# stm32.net
KiCad netlist of a schematic drawn in EasyEDA Pro
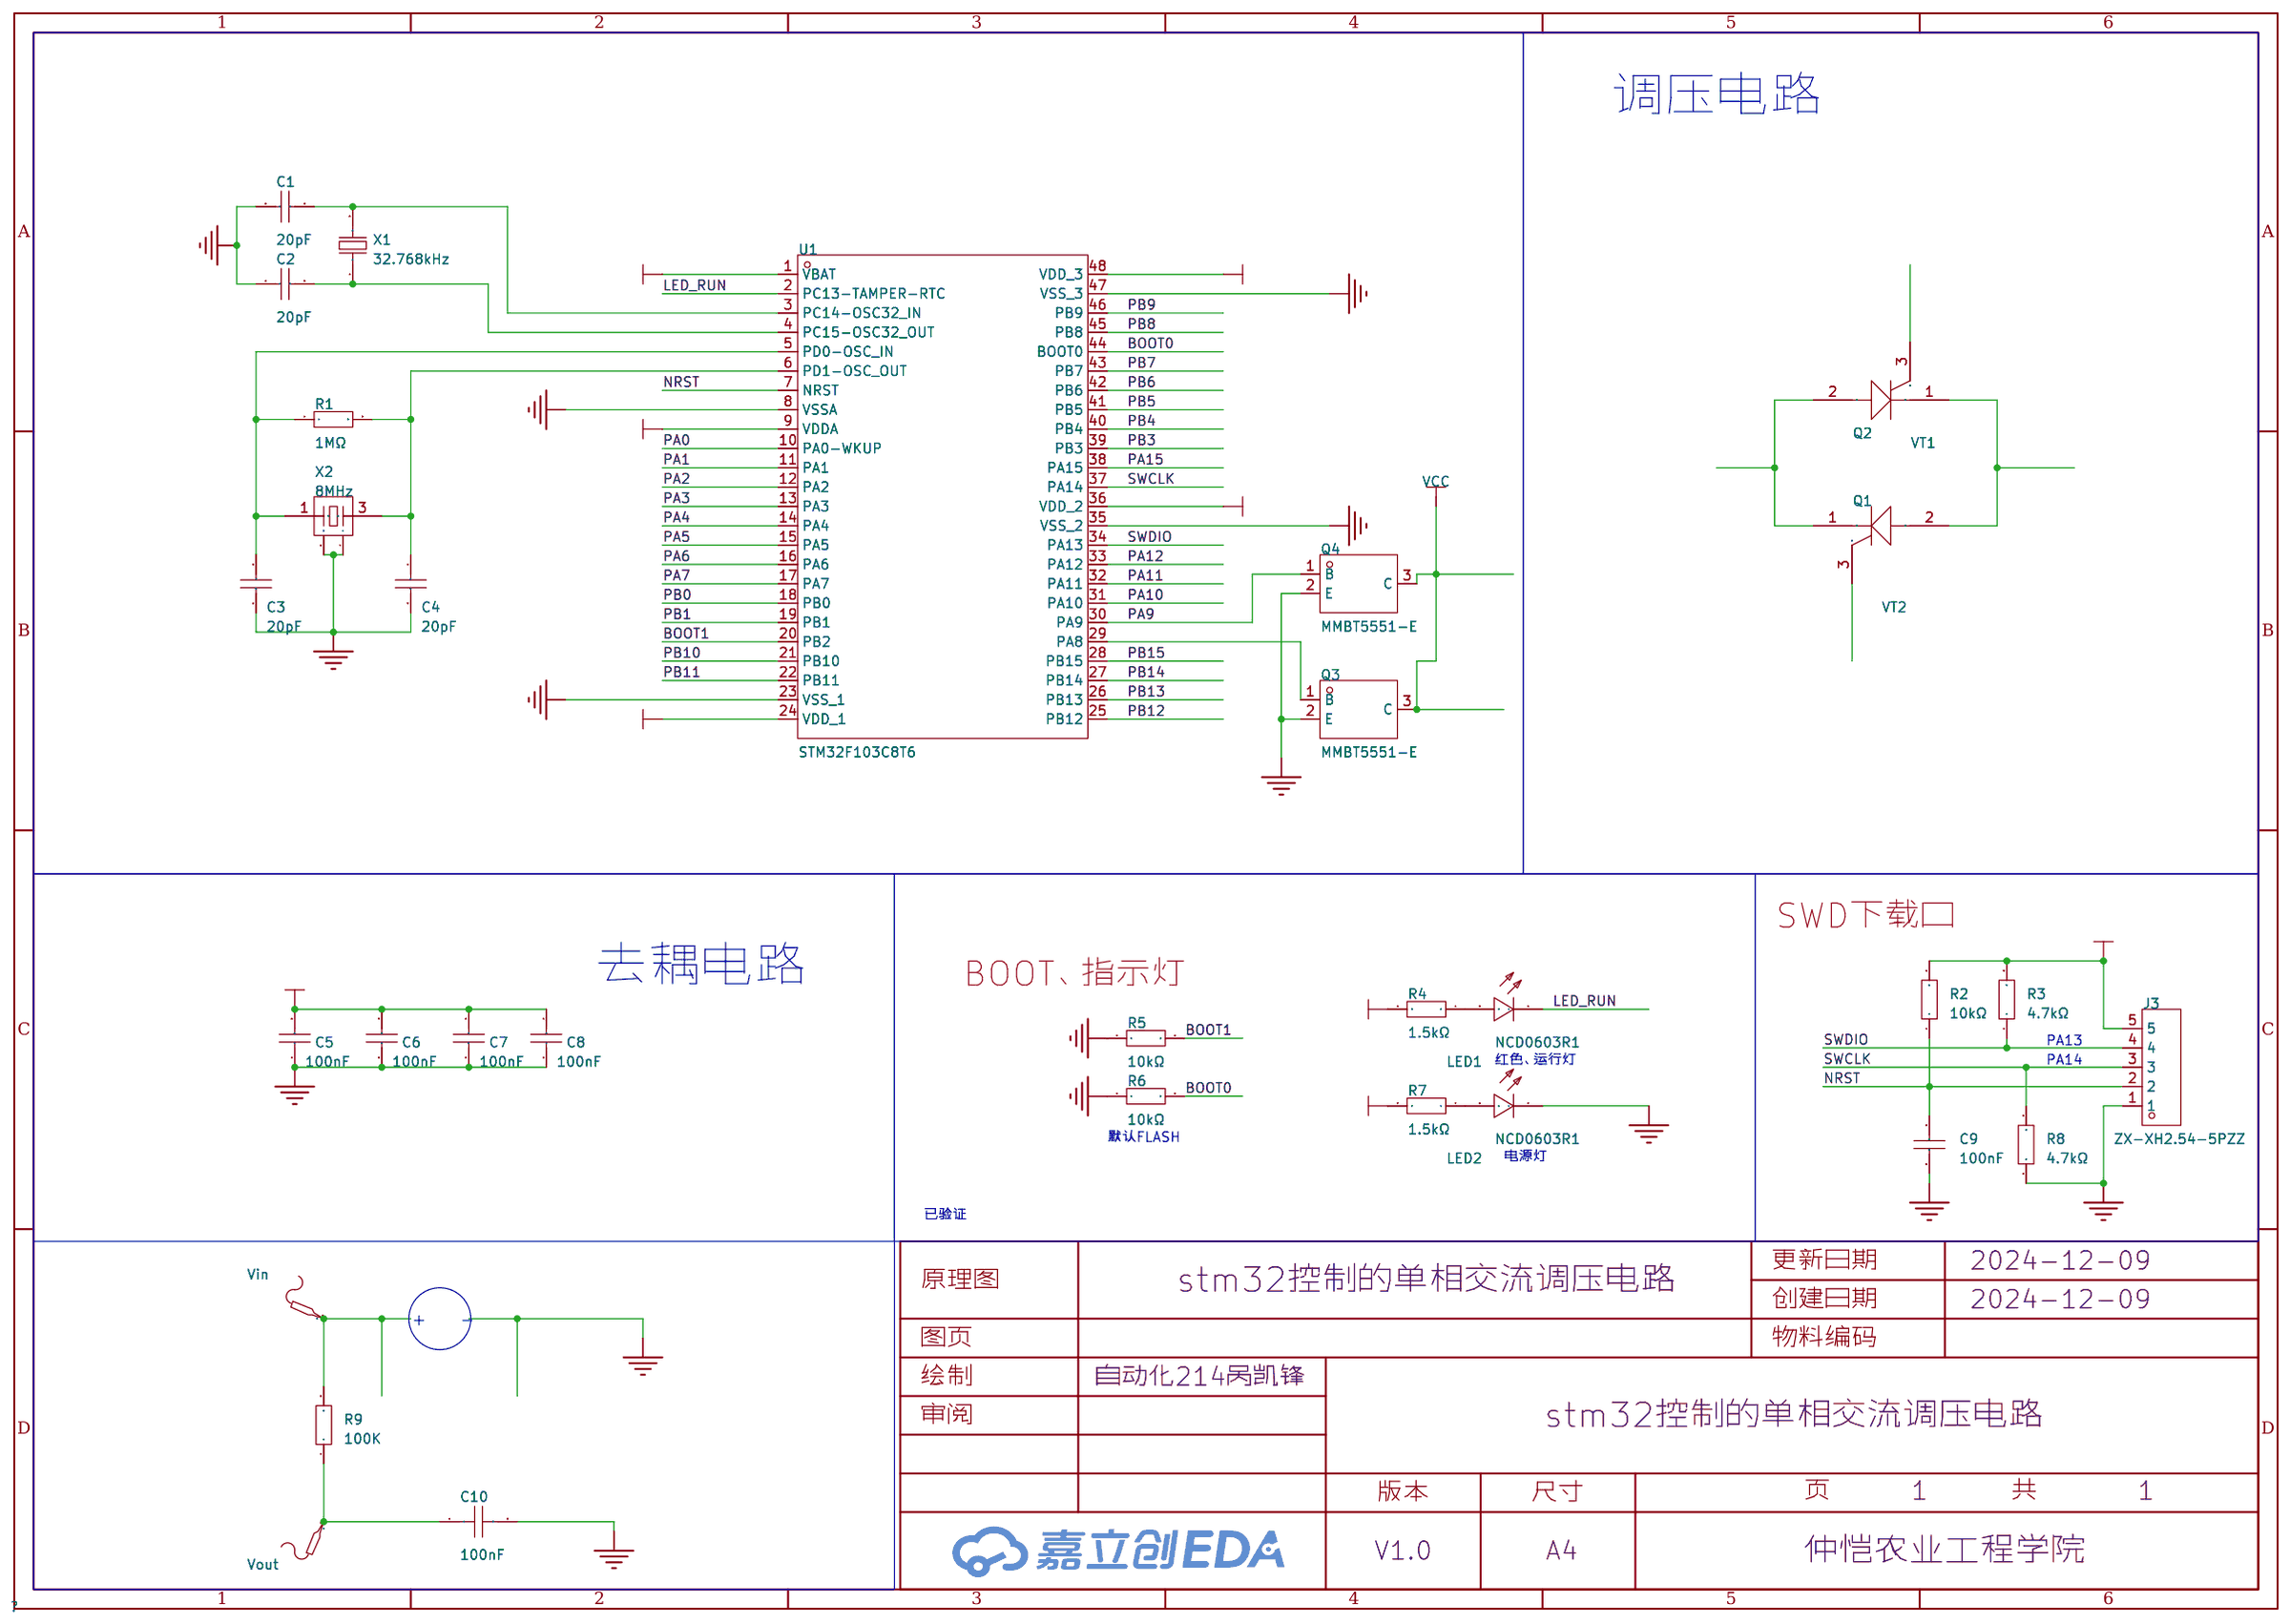
[diagram p0: schematic sheet]

(export (version "E")
  (design (tool "Eeschema 10.0.6"))
  (components
    (comp (ref "C1")
      (value "20pF")
      (footprint "easyedapro:C0603")
      (description "容值:20pF;精度:±5%;额定电压:50V;材质(温度系数):C0G;")
      (fields
        (field (name "Manufacturer Part") "CL10C200JB8NNNC")
        (field (name "Manufacturer") "SAMSUNG(三星)")
      )
      (libsource (lib "easyedapro") (part "CL10C200JB8NNNC"))
    )
    (comp (ref "C2")
      (value "20pF")
      (footprint "easyedapro:C0603")
      (description "容值:20pF;精度:±5%;额定电压:50V;材质(温度系数):C0G;")
      (fields
        (field (name "Manufacturer Part") "CL10C200JB8NNNC")
        (field (name "Manufacturer") "SAMSUNG(三星)")
      )
      (libsource (lib "easyedapro") (part "CL10C200JB8NNNC"))
    )
    (comp (ref "C3")
      (value "20pF")
      (footprint "easyedapro:C0603")
      (description "容值:20pF;精度:±5%;额定电压:50V;材质(温度系数):C0G;")
      (fields
        (field (name "Manufacturer Part") "CL10C200JB8NNNC")
        (field (name "Manufacturer") "SAMSUNG(三星)")
      )
      (libsource (lib "easyedapro") (part "CL10C200JB8NNNC"))
    )
    (comp (ref "C4")
      (value "20pF")
      (footprint "easyedapro:C0603")
      (description "容值:20pF;精度:±5%;额定电压:50V;材质(温度系数):C0G;")
      (fields
        (field (name "Manufacturer Part") "CL10C200JB8NNNC")
        (field (name "Manufacturer") "SAMSUNG(三星)")
      )
      (libsource (lib "easyedapro") (part "CL10C200JB8NNNC"))
    )
    (comp (ref "C5")
      (value "100nF")
      (footprint "easyedapro:C0603")
      (description "容值:100nF;精度:±10%;额定电压:50V;材质(温度系数):X7R;")
      (fields
        (field (name "Manufacturer Part") "CC0603KRX7R9BB104")
        (field (name "Manufacturer") "YAGEO(国巨)")
      )
      (libsource (lib "easyedapro") (part "CC0603KRX7R9BB104"))
    )
    (comp (ref "C6")
      (value "100nF")
      (footprint "easyedapro:C0603")
      (description "容值:100nF;精度:±10%;额定电压:50V;材质(温度系数):X7R;")
      (fields
        (field (name "Manufacturer Part") "CC0603KRX7R9BB104")
        (field (name "Manufacturer") "YAGEO(国巨)")
      )
      (libsource (lib "easyedapro") (part "CC0603KRX7R9BB104"))
    )
    (comp (ref "C7")
      (value "100nF")
      (footprint "easyedapro:C0603")
      (description "容值:100nF;精度:±10%;额定电压:50V;材质(温度系数):X7R;")
      (fields
        (field (name "Manufacturer Part") "CC0603KRX7R9BB104")
        (field (name "Manufacturer") "YAGEO(国巨)")
      )
      (libsource (lib "easyedapro") (part "CC0603KRX7R9BB104"))
    )
    (comp (ref "C8")
      (value "100nF")
      (footprint "easyedapro:C0603")
      (description "容值:100nF;精度:±10%;额定电压:50V;材质(温度系数):X7R;")
      (fields
        (field (name "Manufacturer Part") "CC0603KRX7R9BB104")
        (field (name "Manufacturer") "YAGEO(国巨)")
      )
      (libsource (lib "easyedapro") (part "CC0603KRX7R9BB104"))
    )
    (comp (ref "C9")
      (value "100nF")
      (footprint "easyedapro:C0603")
      (description "容值:100nF;精度:±10%;额定电压:50V;材质(温度系数):X7R;")
      (fields
        (field (name "Manufacturer Part") "CC0603KRX7R9BB104")
        (field (name "Manufacturer") "YAGEO(国巨)")
      )
      (libsource (lib "easyedapro") (part "CC0603KRX7R9BB104"))
    )
    (comp (ref "C10")
      (value "100nF")
      (footprint "easyedapro:C0603")
      (libsource (lib "easyedapro") (part "CapAcitance"))
    )
    (comp (ref "J3")
      (value "ZX-XH2.54-5PZZ")
      (footprint "easyedapro:CONN-TH_5P-P2.50_ZX-XH2.54-5PZZ")
      (fields (field (name "Manufacturer") "Megastar(兆星)"))
      (libsource (lib "easyedapro") (part "ZX-XH2.54-5PZZ"))
    )
    (comp (ref "LED1")
      (value "NCD0603R1")
      (footprint "easyedapro:LED0603-RD_RED")
      (fields (field (name "Manufacturer") "国星光电"))
      (libsource (lib "easyedapro") (part "FC-DA1608HRK-620D"))
    )
    (comp (ref "LED2")
      (value "NCD0603R1")
      (footprint "easyedapro:LED0603-RD_RED")
      (fields (field (name "Manufacturer") "国星光电"))
      (libsource (lib "easyedapro") (part "FC-DA1608HRK-620D"))
    )
    (comp (ref "Q1")
      (value "VT2")
      (footprint "easyedapro:DPAK-3_L6.6-W6.1-P2.28-LS9.9-BR")
      (description "可控硅类型:1个单向可控硅;保持电流(Ih):20mA;断态峰值电压(Vdrm):500V;门极触发电流(Igt):15mA;")
      (fields (field (name "Manufacturer") "WeEn(瑞能)"))
      (libsource (lib "easyedapro") (part "BT151S-500R,118"))
    )
    (comp (ref "Q2")
      (value "VT1")
      (footprint "easyedapro:DPAK-3_L6.6-W6.1-P2.28-LS9.9-BR")
      (description "可控硅类型:1个单向可控硅;保持电流(Ih):20mA;断态峰值电压(Vdrm):500V;门极触发电流(Igt):15mA;")
      (fields (field (name "Manufacturer") "WeEn(瑞能)"))
      (libsource (lib "easyedapro") (part "BT151S-500R,118"))
    )
    (comp (ref "Q3")
      (value "MMBT5551-E")
      (footprint "easyedapro:SOT-23-3_L2.9-W1.8-P1.90-LS2.4-BR")
      (description "晶体管类型:NPN;集电极电流(Ic):600mA;集射极击穿电压(Vceo):160V;功率(Pd):300mW;直流电流增益(hFE@Ic,Vce):80@1mA,5V;")
      (fields (field (name "Manufacturer") "MDD(辰达半导体)"))
      (libsource (lib "easyedapro") (part "MMBT5551-E"))
    )
    (comp (ref "Q4")
      (value "MMBT5551-E")
      (footprint "easyedapro:SOT-23-3_L2.9-W1.8-P1.90-LS2.4-BR")
      (description "晶体管类型:NPN;集电极电流(Ic):600mA;集射极击穿电压(Vceo):160V;功率(Pd):300mW;直流电流增益(hFE@Ic,Vce):80@1mA,5V;")
      (fields (field (name "Manufacturer") "MDD(辰达半导体)"))
      (libsource (lib "easyedapro") (part "MMBT5551-E"))
    )
    (comp (ref "R1")
      (value "1MΩ")
      (footprint "easyedapro:R0603")
      (description "电阻类型:厚膜电阻;阻值:1MΩ;精度:±1%;功率:100mW;最大工作电压:75V;温度系数:±100ppm/°C;")
      (fields
        (field (name "Manufacturer Part") "0603WAF1004T5E")
        (field (name "Manufacturer") "UNI-ROYAL(厚声)")
      )
      (libsource (lib "easyedapro") (part "0603WAF1004T5E"))
    )
    (comp (ref "R2")
      (value "10kΩ")
      (footprint "easyedapro:R0603")
      (description "电阻类型:厚膜电阻;阻值:10kΩ;精度:±1%;功率:100mW;最大工作电压:75V;温度系数:±100ppm/°C;")
      (fields
        (field (name "Manufacturer Part") "0603WAF1002T5E")
        (field (name "Manufacturer") "UNI-ROYAL(厚声)")
      )
      (libsource (lib "easyedapro") (part "0603WAF1002T5E"))
    )
    (comp (ref "R3")
      (value "4.7kΩ")
      (footprint "easyedapro:R0603")
      (description "电阻类型:厚膜电阻;阻值:4.7kΩ;精度:±1%;功率:100mW;最大工作电压:75V;温度系数:±100ppm/°C;")
      (fields
        (field (name "Manufacturer Part") "0603WAF4701T5E")
        (field (name "Manufacturer") "UNI-ROYAL(厚声)")
      )
      (libsource (lib "easyedapro") (part "0603WAF4701T5E"))
    )
    (comp (ref "R4")
      (value "1.5kΩ")
      (footprint "easyedapro:R0603")
      (description "电阻类型:厚膜电阻;阻值:1.5kΩ;精度:±1%;功率:100mW;最大工作电压:75V;温度系数:±100ppm/°C;")
      (fields
        (field (name "Manufacturer Part") "0603WAF1501T5E")
        (field (name "Manufacturer") "UNI-ROYAL(厚声)")
      )
      (libsource (lib "easyedapro") (part "0603WAF1501T5E"))
    )
    (comp (ref "R5")
      (value "10kΩ")
      (footprint "easyedapro:R0603")
      (description "电阻类型:厚膜电阻;阻值:10kΩ;精度:±1%;功率:100mW;最大工作电压:75V;温度系数:±100ppm/°C;")
      (fields
        (field (name "Manufacturer Part") "0603WAF1002T5E")
        (field (name "Manufacturer") "UNI-ROYAL(厚声)")
      )
      (libsource (lib "easyedapro") (part "0603WAF1002T5E"))
    )
    (comp (ref "R6")
      (value "10kΩ")
      (footprint "easyedapro:R0603")
      (description "电阻类型:厚膜电阻;阻值:10kΩ;精度:±1%;功率:100mW;最大工作电压:75V;温度系数:±100ppm/°C;")
      (fields
        (field (name "Manufacturer Part") "0603WAF1002T5E")
        (field (name "Manufacturer") "UNI-ROYAL(厚声)")
      )
      (libsource (lib "easyedapro") (part "0603WAF1002T5E"))
    )
    (comp (ref "R7")
      (value "1.5kΩ")
      (footprint "easyedapro:R0603")
      (description "电阻类型:厚膜电阻;阻值:1.5kΩ;精度:±1%;功率:100mW;最大工作电压:75V;温度系数:±100ppm/°C;")
      (fields
        (field (name "Manufacturer Part") "0603WAF1501T5E")
        (field (name "Manufacturer") "UNI-ROYAL(厚声)")
      )
      (libsource (lib "easyedapro") (part "0603WAF1501T5E"))
    )
    (comp (ref "R8")
      (value "4.7kΩ")
      (footprint "easyedapro:R0603")
      (description "电阻类型:厚膜电阻;阻值:4.7kΩ;精度:±1%;功率:100mW;最大工作电压:75V;温度系数:±100ppm/°C;")
      (fields
        (field (name "Manufacturer Part") "0603WAF4701T5E")
        (field (name "Manufacturer") "UNI-ROYAL(厚声)")
      )
      (libsource (lib "easyedapro") (part "0603WAF4701T5E"))
    )
    (comp (ref "R9") (value "100K") (footprint "easyedapro:R0603") (libsource (lib "easyedapro") (part "电阻")))
    (comp (ref "U1")
      (value "STM32F103C8T6")
      (footprint "easyedapro:LQFP-48_L7.0-W7.0-P0.50-LS9.0-BL")
      (description "CPU内核:ARM-M3;程序存储容量:64KB;RAM总容量:20KB;GPIO端口数量:37;工作电压范围:2V~3.6V;CPU最大主频:72MHz;程序存储器类型:FLASH;")
      (fields (field (name "Manufacturer") "ST(意法半导体)"))
      (libsource (lib "easyedapro") (part "STM32F103C8T6"))
    )
    (comp (ref "Vin")
      (value "~")
      (footprint "easyedapro:Test-Point-0.5mm")
      (description "Test Point 测试点")
      (libsource (lib "easyedapro") (part "Test-Point"))
    )
    (comp (ref "Vout")
      (value "~")
      (footprint "easyedapro:Test-Point-0.5mm")
      (description "Test Point 测试点")
      (libsource (lib "easyedapro") (part "Test-Point"))
    )
    (comp (ref "X1")
      (value "32.768kHz")
      (footprint "easyedapro:FC-135R_L3.2-W1.5")
      (description "晶振类型:贴片晶振;频率:32.768kHz;常温频差:±20ppm;外接负载电容:12.5pF;")
      (fields (field (name "Manufacturer Part") "Q13FC13500004") (field (name "Manufacturer") "EPSON(爱普生)"))
      (libsource (lib "easyedapro") (part "Q13FC1350000400"))
    )
    (comp (ref "X2")
      (value "8MHz")
      (fields
        (field (name "Manufacturer Part") "X50328MSB4SI")
        (field (name "Manufacturer") "YXC(扬兴晶振)")
        (field (name "版权归属") "封装库来自淘宝卖家 ID：黄晶宝石")
      )
      (libsource (lib "easyedapro") (part "XTAL-4P"))
    )
  )
  (nets
    (net (code "1") (name "/BOOT0") (class "Default")
      (node (ref "R6") (pin "2") (pinfunction "2_2") (pintype "input"))
      (node (ref "U1") (pin "44") (pinfunction "BOOT0_44") (pintype "unspecified"))
    )
    (net (code "2") (name "/BOOT1") (class "Default")
      (node (ref "R5") (pin "2") (pinfunction "2_2") (pintype "input"))
      (node (ref "U1") (pin "20") (pinfunction "PB2_20") (pintype "unspecified"))
    )
    (net (code "3") (name "/LED_RUN") (class "Default")
      (node (ref "LED1") (pin "1") (pinfunction "K_1") (pintype "input"))
      (node (ref "U1") (pin "2") (pinfunction "PC13-TAMPER-RTC_2") (pintype "unspecified"))
    )
    (net (code "4") (name "/NRST") (class "Default")
      (node (ref "C9") (pin "1") (pinfunction "1_1") (pintype "unspecified"))
      (node (ref "J3") (pin "2") (pinfunction "2_2") (pintype "unspecified"))
      (node (ref "R2") (pin "1") (pinfunction "1_1") (pintype "input"))
      (node (ref "U1") (pin "7") (pinfunction "NRST_7") (pintype "unspecified"))
    )
    (net (code "5") (name "/PA0") (class "Default")
      (node (ref "U1") (pin "10") (pinfunction "PA0-WKUP_10") (pintype "unspecified"))
    )
    (net (code "6") (name "/PA1") (class "Default")
      (node (ref "U1") (pin "11") (pinfunction "PA1_11") (pintype "unspecified"))
    )
    (net (code "7") (name "/PA2") (class "Default")
      (node (ref "U1") (pin "12") (pinfunction "PA2_12") (pintype "unspecified"))
    )
    (net (code "8") (name "/PA3") (class "Default")
      (node (ref "U1") (pin "13") (pinfunction "PA3_13") (pintype "unspecified"))
    )
    (net (code "9") (name "/PA4") (class "Default")
      (node (ref "U1") (pin "14") (pinfunction "PA4_14") (pintype "unspecified"))
    )
    (net (code "10") (name "/PA5") (class "Default")
      (node (ref "U1") (pin "15") (pinfunction "PA5_15") (pintype "unspecified"))
    )
    (net (code "11") (name "/PA6") (class "Default")
      (node (ref "U1") (pin "16") (pinfunction "PA6_16") (pintype "unspecified"))
    )
    (net (code "12") (name "/PA7") (class "Default")
      (node (ref "U1") (pin "17") (pinfunction "PA7_17") (pintype "unspecified"))
    )
    (net (code "13") (name "/PA9") (class "Default")
      (node (ref "Q4") (pin "1") (pinfunction "B_1") (pintype "unspecified"))
      (node (ref "U1") (pin "30") (pinfunction "PA9_30") (pintype "unspecified"))
    )
    (net (code "14") (name "/PA10") (class "Default")
      (node (ref "U1") (pin "31") (pinfunction "PA10_31") (pintype "unspecified"))
    )
    (net (code "15") (name "/PA11") (class "Default")
      (node (ref "U1") (pin "32") (pinfunction "PA11_32") (pintype "unspecified"))
    )
    (net (code "16") (name "/PA12") (class "Default")
      (node (ref "U1") (pin "33") (pinfunction "PA12_33") (pintype "unspecified"))
    )
    (net (code "17") (name "/PA15") (class "Default")
      (node (ref "U1") (pin "38") (pinfunction "PA15_38") (pintype "unspecified"))
    )
    (net (code "18") (name "/PB0") (class "Default")
      (node (ref "U1") (pin "18") (pinfunction "PB0_18") (pintype "unspecified"))
    )
    (net (code "19") (name "/PB1") (class "Default")
      (node (ref "U1") (pin "19") (pinfunction "PB1_19") (pintype "unspecified"))
    )
    (net (code "20") (name "/PB3") (class "Default")
      (node (ref "U1") (pin "39") (pinfunction "PB3_39") (pintype "unspecified"))
    )
    (net (code "21") (name "/PB4") (class "Default")
      (node (ref "U1") (pin "40") (pinfunction "PB4_40") (pintype "unspecified"))
    )
    (net (code "22") (name "/PB5") (class "Default")
      (node (ref "U1") (pin "41") (pinfunction "PB5_41") (pintype "unspecified"))
    )
    (net (code "23") (name "/PB6") (class "Default")
      (node (ref "U1") (pin "42") (pinfunction "PB6_42") (pintype "unspecified"))
    )
    (net (code "24") (name "/PB7") (class "Default")
      (node (ref "U1") (pin "43") (pinfunction "PB7_43") (pintype "unspecified"))
    )
    (net (code "25") (name "/PB8") (class "Default")
      (node (ref "U1") (pin "45") (pinfunction "PB8_45") (pintype "unspecified"))
    )
    (net (code "26") (name "/PB9") (class "Default")
      (node (ref "U1") (pin "46") (pinfunction "PB9_46") (pintype "unspecified"))
    )
    (net (code "27") (name "/PB10") (class "Default")
      (node (ref "U1") (pin "21") (pinfunction "PB10_21") (pintype "unspecified"))
    )
    (net (code "28") (name "/PB11") (class "Default")
      (node (ref "U1") (pin "22") (pinfunction "PB11_22") (pintype "unspecified"))
    )
    (net (code "29") (name "/PB12") (class "Default")
      (node (ref "U1") (pin "25") (pinfunction "PB12_25") (pintype "unspecified"))
    )
    (net (code "30") (name "/PB13") (class "Default")
      (node (ref "U1") (pin "26") (pinfunction "PB13_26") (pintype "unspecified"))
    )
    (net (code "31") (name "/PB14") (class "Default")
      (node (ref "U1") (pin "27") (pinfunction "PB14_27") (pintype "unspecified"))
    )
    (net (code "32") (name "/PB15") (class "Default")
      (node (ref "U1") (pin "28") (pinfunction "PB15_28") (pintype "unspecified"))
    )
    (net (code "33") (name "/SWCLK") (class "Default")
      (node (ref "J3") (pin "3") (pinfunction "3_3") (pintype "unspecified"))
      (node (ref "R8") (pin "2") (pinfunction "2_2") (pintype "input"))
      (node (ref "U1") (pin "37") (pinfunction "PA14_37") (pintype "unspecified"))
    )
    (net (code "34") (name "/SWDIO") (class "Default")
      (node (ref "J3") (pin "4") (pinfunction "4_4") (pintype "unspecified"))
      (node (ref "R3") (pin "1") (pinfunction "1_1") (pintype "input"))
      (node (ref "U1") (pin "34") (pinfunction "PA13_34") (pintype "unspecified"))
    )
    (net (code "35") (name "GND") (class "Default")
      (node (ref "C1") (pin "1") (pinfunction "1_1") (pintype "input"))
      (node (ref "C10") (pin "2") (pinfunction "2_2") (pintype "input"))
      (node (ref "C2") (pin "1") (pinfunction "1_1") (pintype "input"))
      (node (ref "C3") (pin "2") (pinfunction "2_2") (pintype "input"))
      (node (ref "C4") (pin "2") (pinfunction "2_2") (pintype "input"))
      (node (ref "C5") (pin "1") (pinfunction "1_1") (pintype "unspecified"))
      (node (ref "C6") (pin "1") (pinfunction "1_1") (pintype "unspecified"))
      (node (ref "C7") (pin "1") (pinfunction "1_1") (pintype "unspecified"))
      (node (ref "C8") (pin "1") (pinfunction "1_1") (pintype "unspecified"))
      (node (ref "C9") (pin "2") (pinfunction "2_2") (pintype "unspecified"))
      (node (ref "J3") (pin "1") (pinfunction "1_1") (pintype "unspecified"))
      (node (ref "LED2") (pin "1") (pinfunction "K_1") (pintype "input"))
      (node (ref "Q3") (pin "2") (pinfunction "E_2") (pintype "unspecified"))
      (node (ref "Q4") (pin "2") (pinfunction "E_2") (pintype "unspecified"))
      (node (ref "R5") (pin "1") (pinfunction "1_1") (pintype "input"))
      (node (ref "R6") (pin "1") (pinfunction "1_1") (pintype "input"))
      (node (ref "R8") (pin "1") (pinfunction "1_1") (pintype "input"))
      (node (ref "U1") (pin "23") (pinfunction "VSS_1_23") (pintype "unspecified"))
      (node (ref "U1") (pin "35") (pinfunction "VSS_2_35") (pintype "unspecified"))
      (node (ref "U1") (pin "47") (pinfunction "VSS_3_47") (pintype "unspecified"))
      (node (ref "U1") (pin "8") (pinfunction "VSSA_8") (pintype "unspecified"))
      (node (ref "X2") (pin "2") (pinfunction "2_2") (pintype "unspecified"))
      (node (ref "X2") (pin "4") (pinfunction "4_4") (pintype "unspecified"))
    )
    (net (code "36") (name "Net-(C10-Pad1)") (class "Default")
      (node (ref "C10") (pin "1") (pinfunction "1_1") (pintype "input"))
      (node (ref "R9") (pin "1") (pinfunction "1_1") (pintype "input"))
      (node (ref "Vout") (pin "1") (pinfunction "1_1") (pintype "input"))
    )
    (net (code "37") (name "Net-(LED1-A)") (class "Default")
      (node (ref "LED1") (pin "2") (pinfunction "A_2") (pintype "input"))
      (node (ref "R4") (pin "1") (pinfunction "1_1") (pintype "input"))
    )
    (net (code "38") (name "Net-(LED2-A)") (class "Default")
      (node (ref "LED2") (pin "2") (pinfunction "A_2") (pintype "input"))
      (node (ref "R7") (pin "1") (pinfunction "1_1") (pintype "input"))
    )
    (net (code "39") (name "Net-(Q1-A)") (class "Default")
      (node (ref "Q1") (pin "2") (pinfunction "A_2") (pintype "unspecified"))
      (node (ref "Q2") (pin "1") (pinfunction "K_1") (pintype "unspecified"))
    )
    (net (code "40") (name "Net-(Q1-K)") (class "Default")
      (node (ref "Q1") (pin "1") (pinfunction "K_1") (pintype "unspecified"))
      (node (ref "Q2") (pin "2") (pinfunction "A_2") (pintype "unspecified"))
    )
    (net (code "41") (name "Net-(Q3-B)") (class "Default")
      (node (ref "Q3") (pin "1") (pinfunction "B_1") (pintype "unspecified"))
      (node (ref "U1") (pin "29") (pinfunction "PA8_29") (pintype "unspecified"))
    )
    (net (code "42") (name "Net-(R9-Pad2)") (class "Default")
      (node (ref "R9") (pin "2") (pinfunction "2_2") (pintype "input"))
      (node (ref "Vin") (pin "1") (pinfunction "1_1") (pintype "input"))
    )
    (net (code "43") (name "Net-(U1-PC14-OSC32_IN)") (class "Default")
      (node (ref "C1") (pin "2") (pinfunction "2_2") (pintype "input"))
      (node (ref "U1") (pin "3") (pinfunction "PC14-OSC32_IN_3") (pintype "unspecified"))
      (node (ref "X1") (pin "2") (pinfunction "2_2") (pintype "unspecified"))
    )
    (net (code "44") (name "Net-(U1-PC15-OSC32_OUT)") (class "Default")
      (node (ref "C2") (pin "2") (pinfunction "2_2") (pintype "input"))
      (node (ref "U1") (pin "4") (pinfunction "PC15-OSC32_OUT_4") (pintype "unspecified"))
      (node (ref "X1") (pin "1") (pinfunction "1_1") (pintype "unspecified"))
    )
    (net (code "45") (name "Net-(U1-PD0-OSC_IN)") (class "Default")
      (node (ref "C3") (pin "1") (pinfunction "1_1") (pintype "input"))
      (node (ref "R1") (pin "1") (pinfunction "1_1") (pintype "input"))
      (node (ref "U1") (pin "5") (pinfunction "PD0-OSC_IN_5") (pintype "unspecified"))
      (node (ref "X2") (pin "1") (pinfunction "1_1") (pintype "unspecified"))
    )
    (net (code "46") (name "Net-(U1-PD1-OSC_OUT)") (class "Default")
      (node (ref "C4") (pin "1") (pinfunction "1_1") (pintype "input"))
      (node (ref "R1") (pin "2") (pinfunction "2_2") (pintype "input"))
      (node (ref "U1") (pin "6") (pinfunction "PD1-OSC_OUT_6") (pintype "unspecified"))
      (node (ref "X2") (pin "3") (pinfunction "3_3") (pintype "unspecified"))
    )
    (net (code "47") (name "VCC") (class "Default")
      (node (ref "Q3") (pin "3") (pinfunction "C_3") (pintype "unspecified"))
      (node (ref "Q4") (pin "3") (pinfunction "C_3") (pintype "unspecified"))
    )
    (net (code "48") (name "VDD_3V3") (class "Default")
      (node (ref "C5") (pin "2") (pinfunction "2_2") (pintype "unspecified"))
      (node (ref "C6") (pin "2") (pinfunction "2_2") (pintype "unspecified"))
      (node (ref "C7") (pin "2") (pinfunction "2_2") (pintype "unspecified"))
      (node (ref "C8") (pin "2") (pinfunction "2_2") (pintype "unspecified"))
      (node (ref "J3") (pin "5") (pinfunction "5_5") (pintype "unspecified"))
      (node (ref "R2") (pin "2") (pinfunction "2_2") (pintype "input"))
      (node (ref "R3") (pin "2") (pinfunction "2_2") (pintype "input"))
      (node (ref "R4") (pin "2") (pinfunction "2_2") (pintype "input"))
      (node (ref "R7") (pin "2") (pinfunction "2_2") (pintype "input"))
      (node (ref "U1") (pin "1") (pinfunction "VBAT_1") (pintype "unspecified"))
      (node (ref "U1") (pin "24") (pinfunction "VDD_1_24") (pintype "unspecified"))
      (node (ref "U1") (pin "36") (pinfunction "VDD_2_36") (pintype "unspecified"))
      (node (ref "U1") (pin "48") (pinfunction "VDD_3_48") (pintype "unspecified"))
      (node (ref "U1") (pin "9") (pinfunction "VDDA_9") (pintype "unspecified"))
    )
    (net (code "49") (name "unconnected-(Q1-G-Pad3)") (class "Default")
      (node (ref "Q1") (pin "3") (pinfunction "G_3") (pintype "unspecified"))
    )
    (net (code "50") (name "unconnected-(Q2-G-Pad3)") (class "Default")
      (node (ref "Q2") (pin "3") (pinfunction "G_3") (pintype "unspecified"))
    )
  )
)
